# SCH_CANSAT-M2-2026.net
KiCad netlist of a schematic drawn in EasyEDA
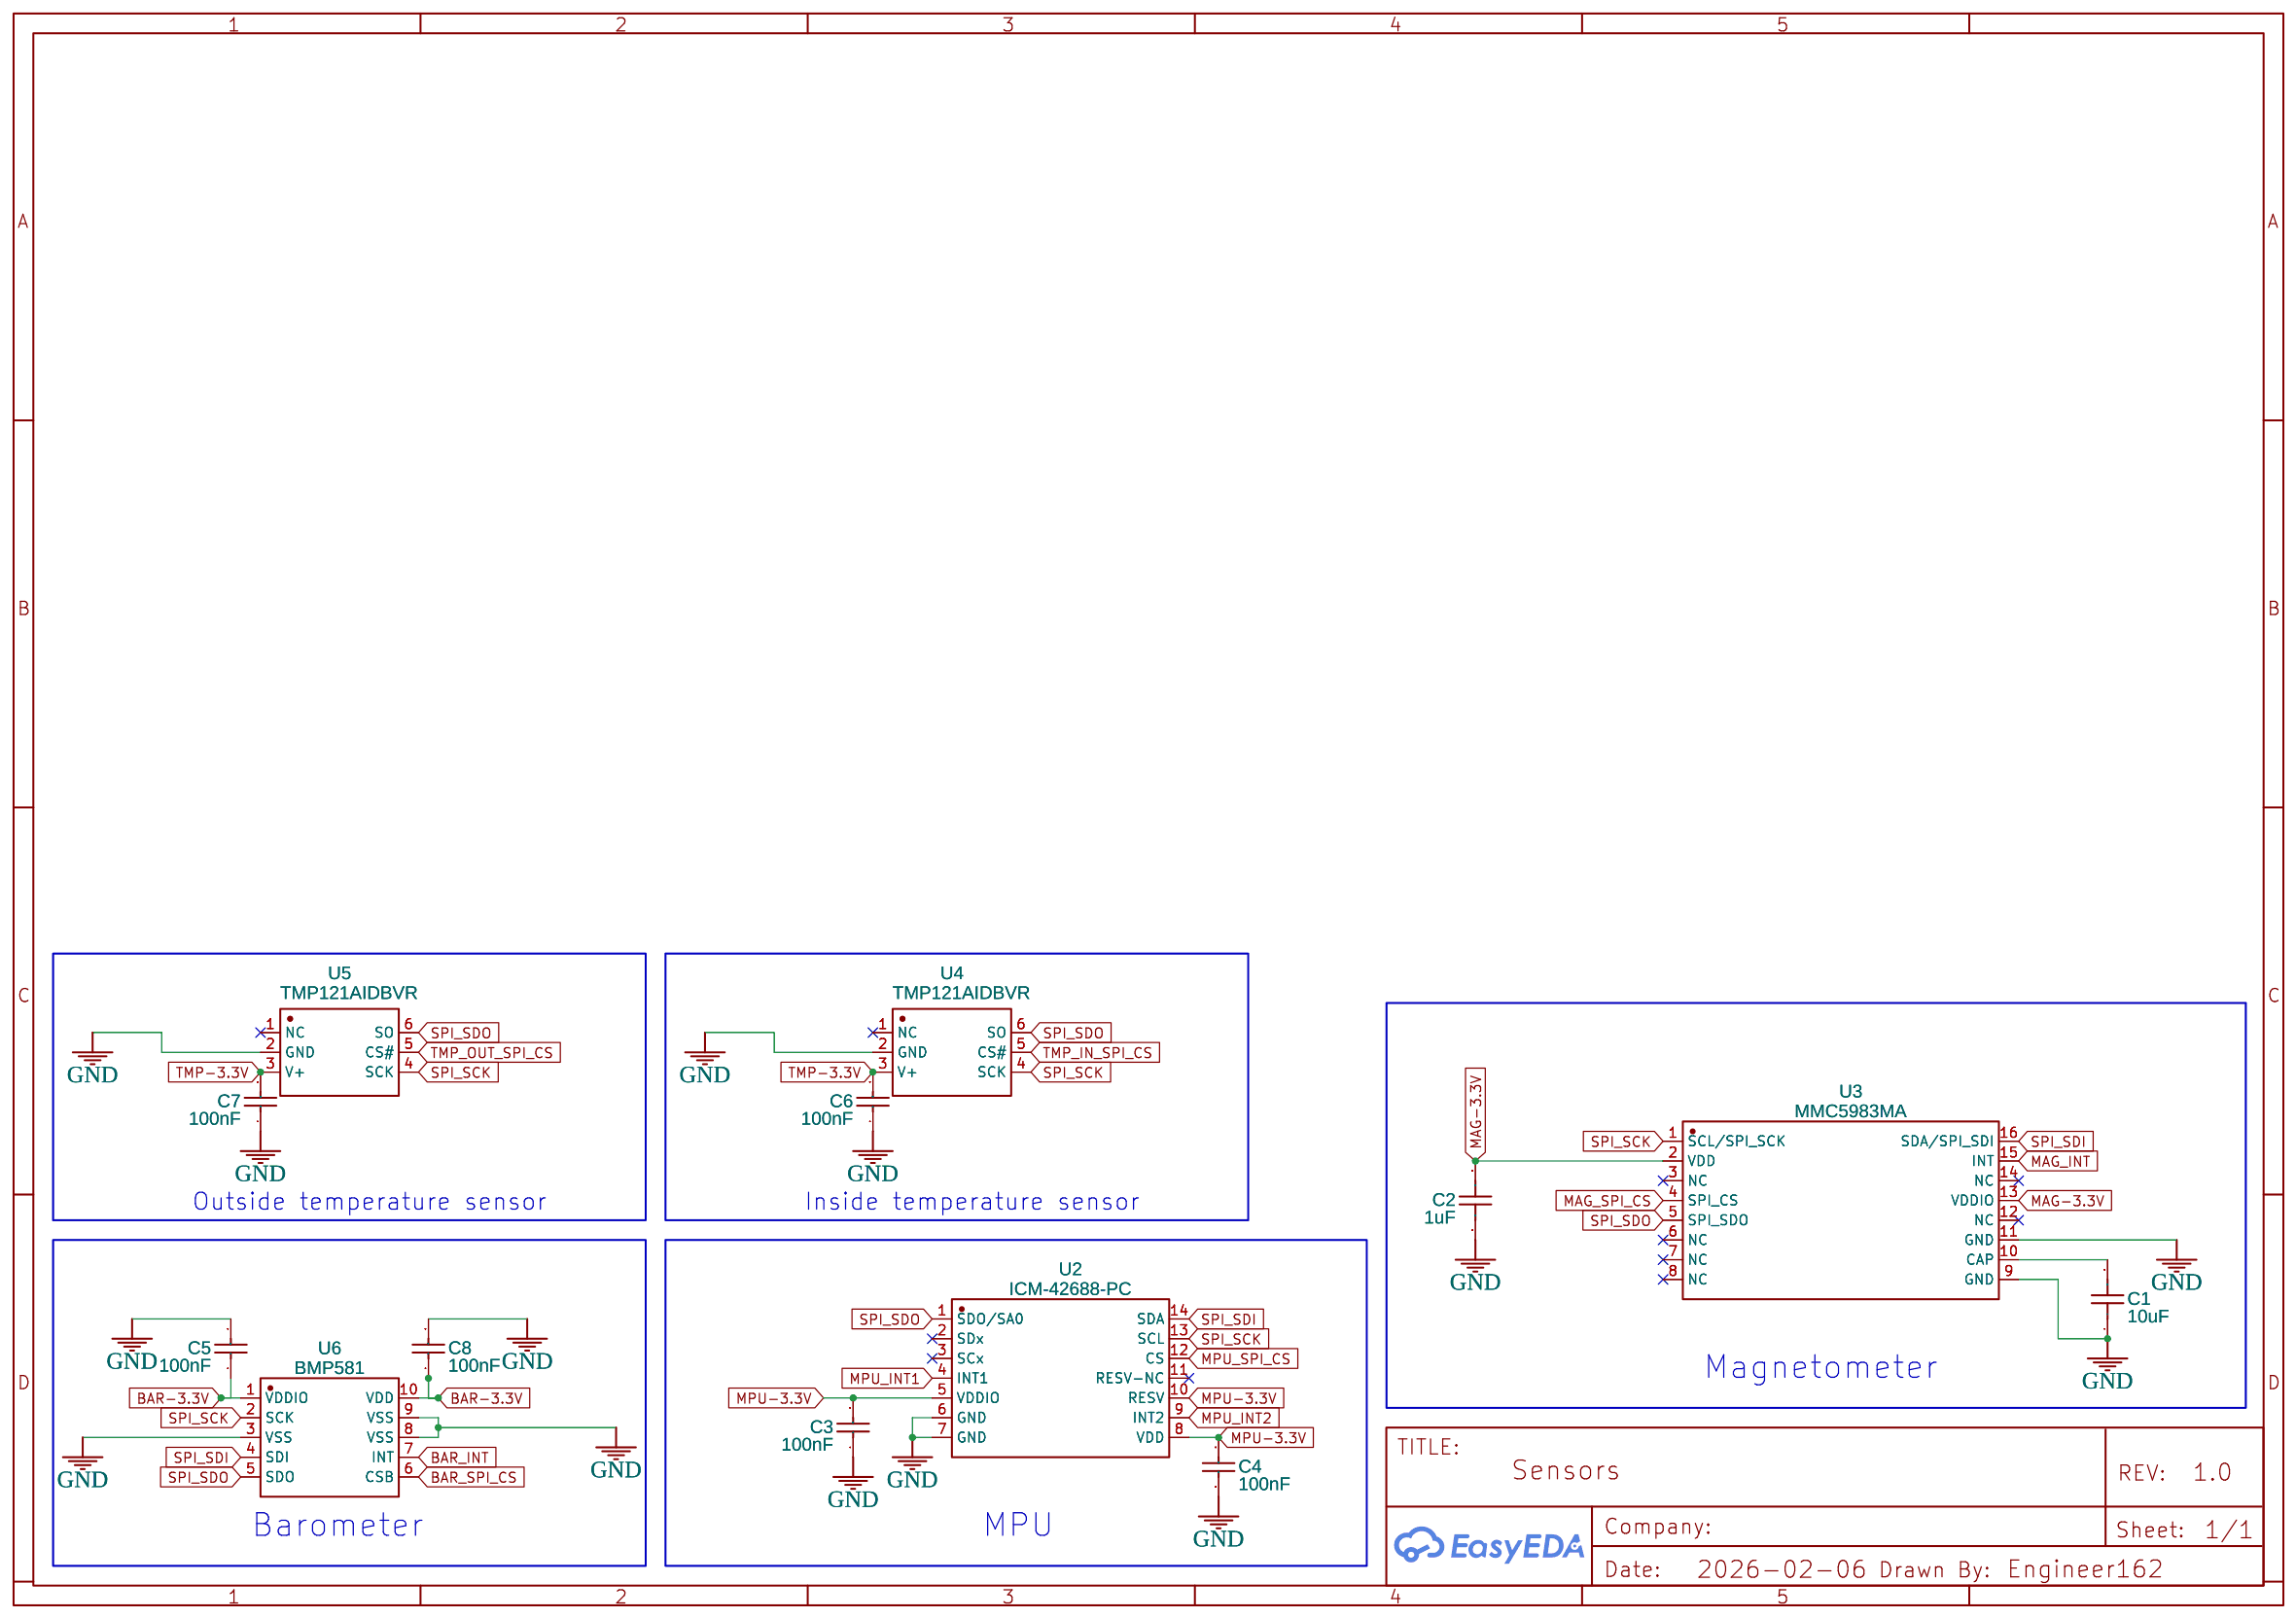
[diagram p0: Sensors]
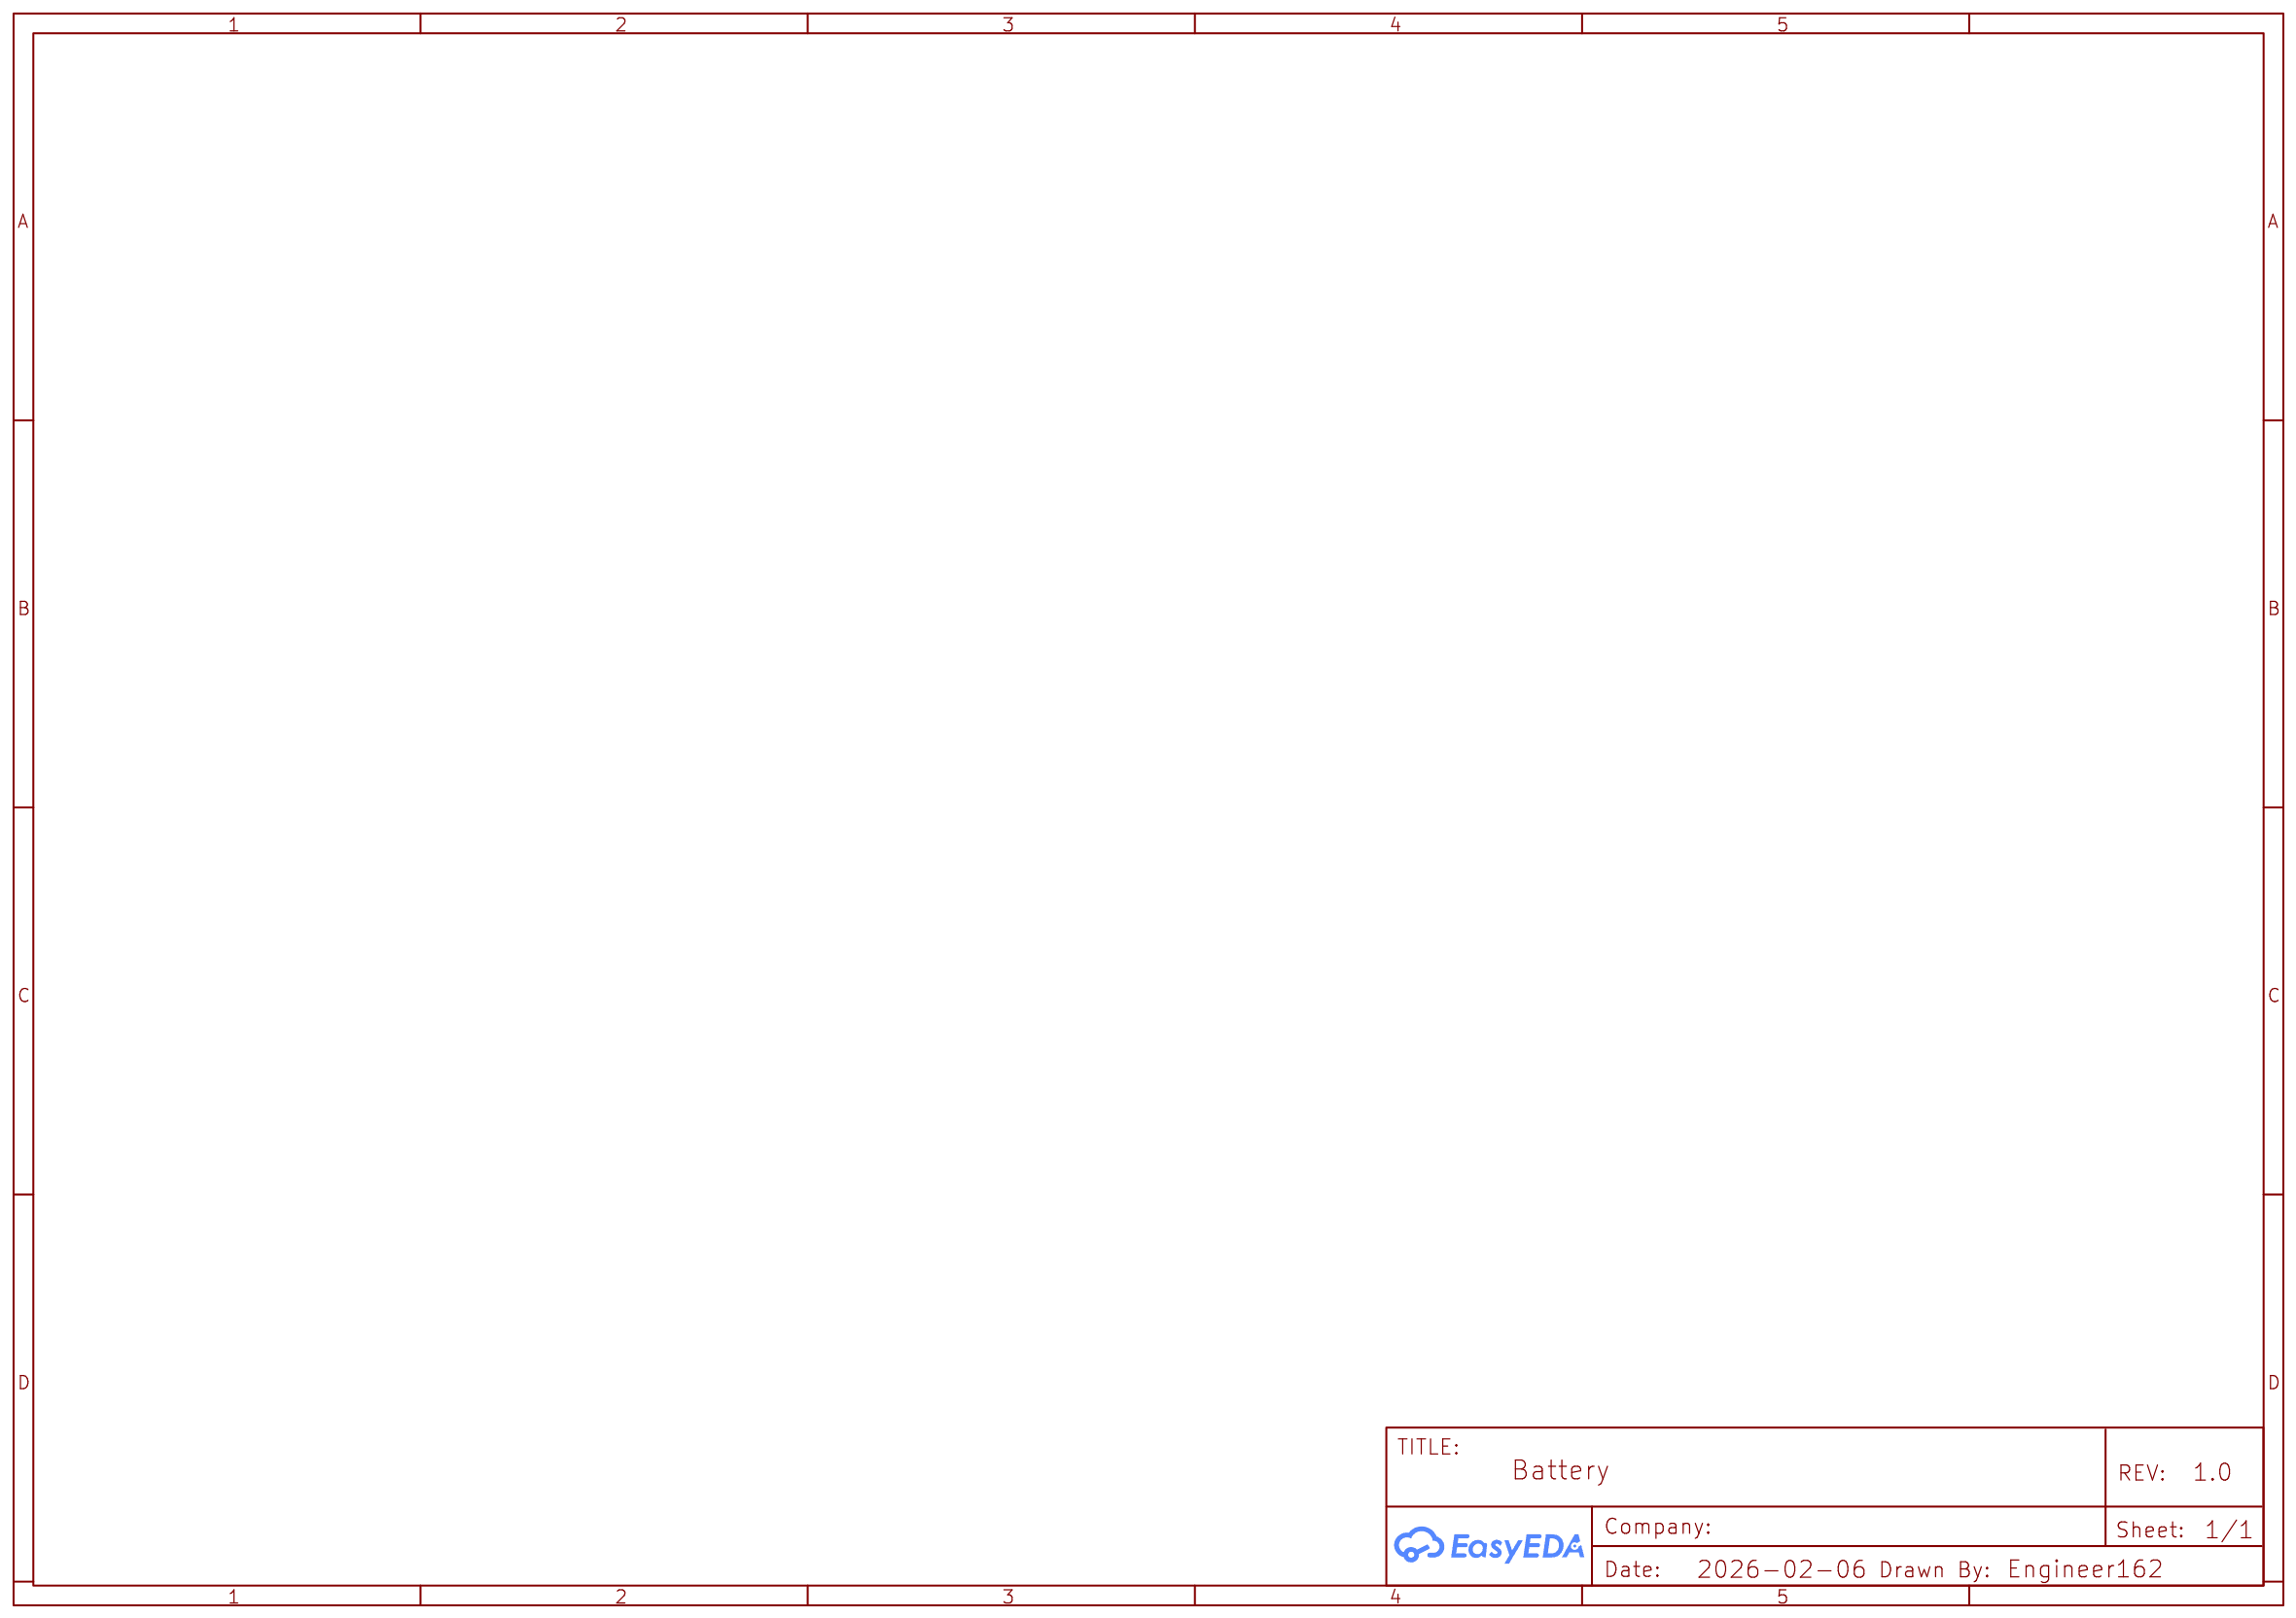
[diagram p1: Battery]
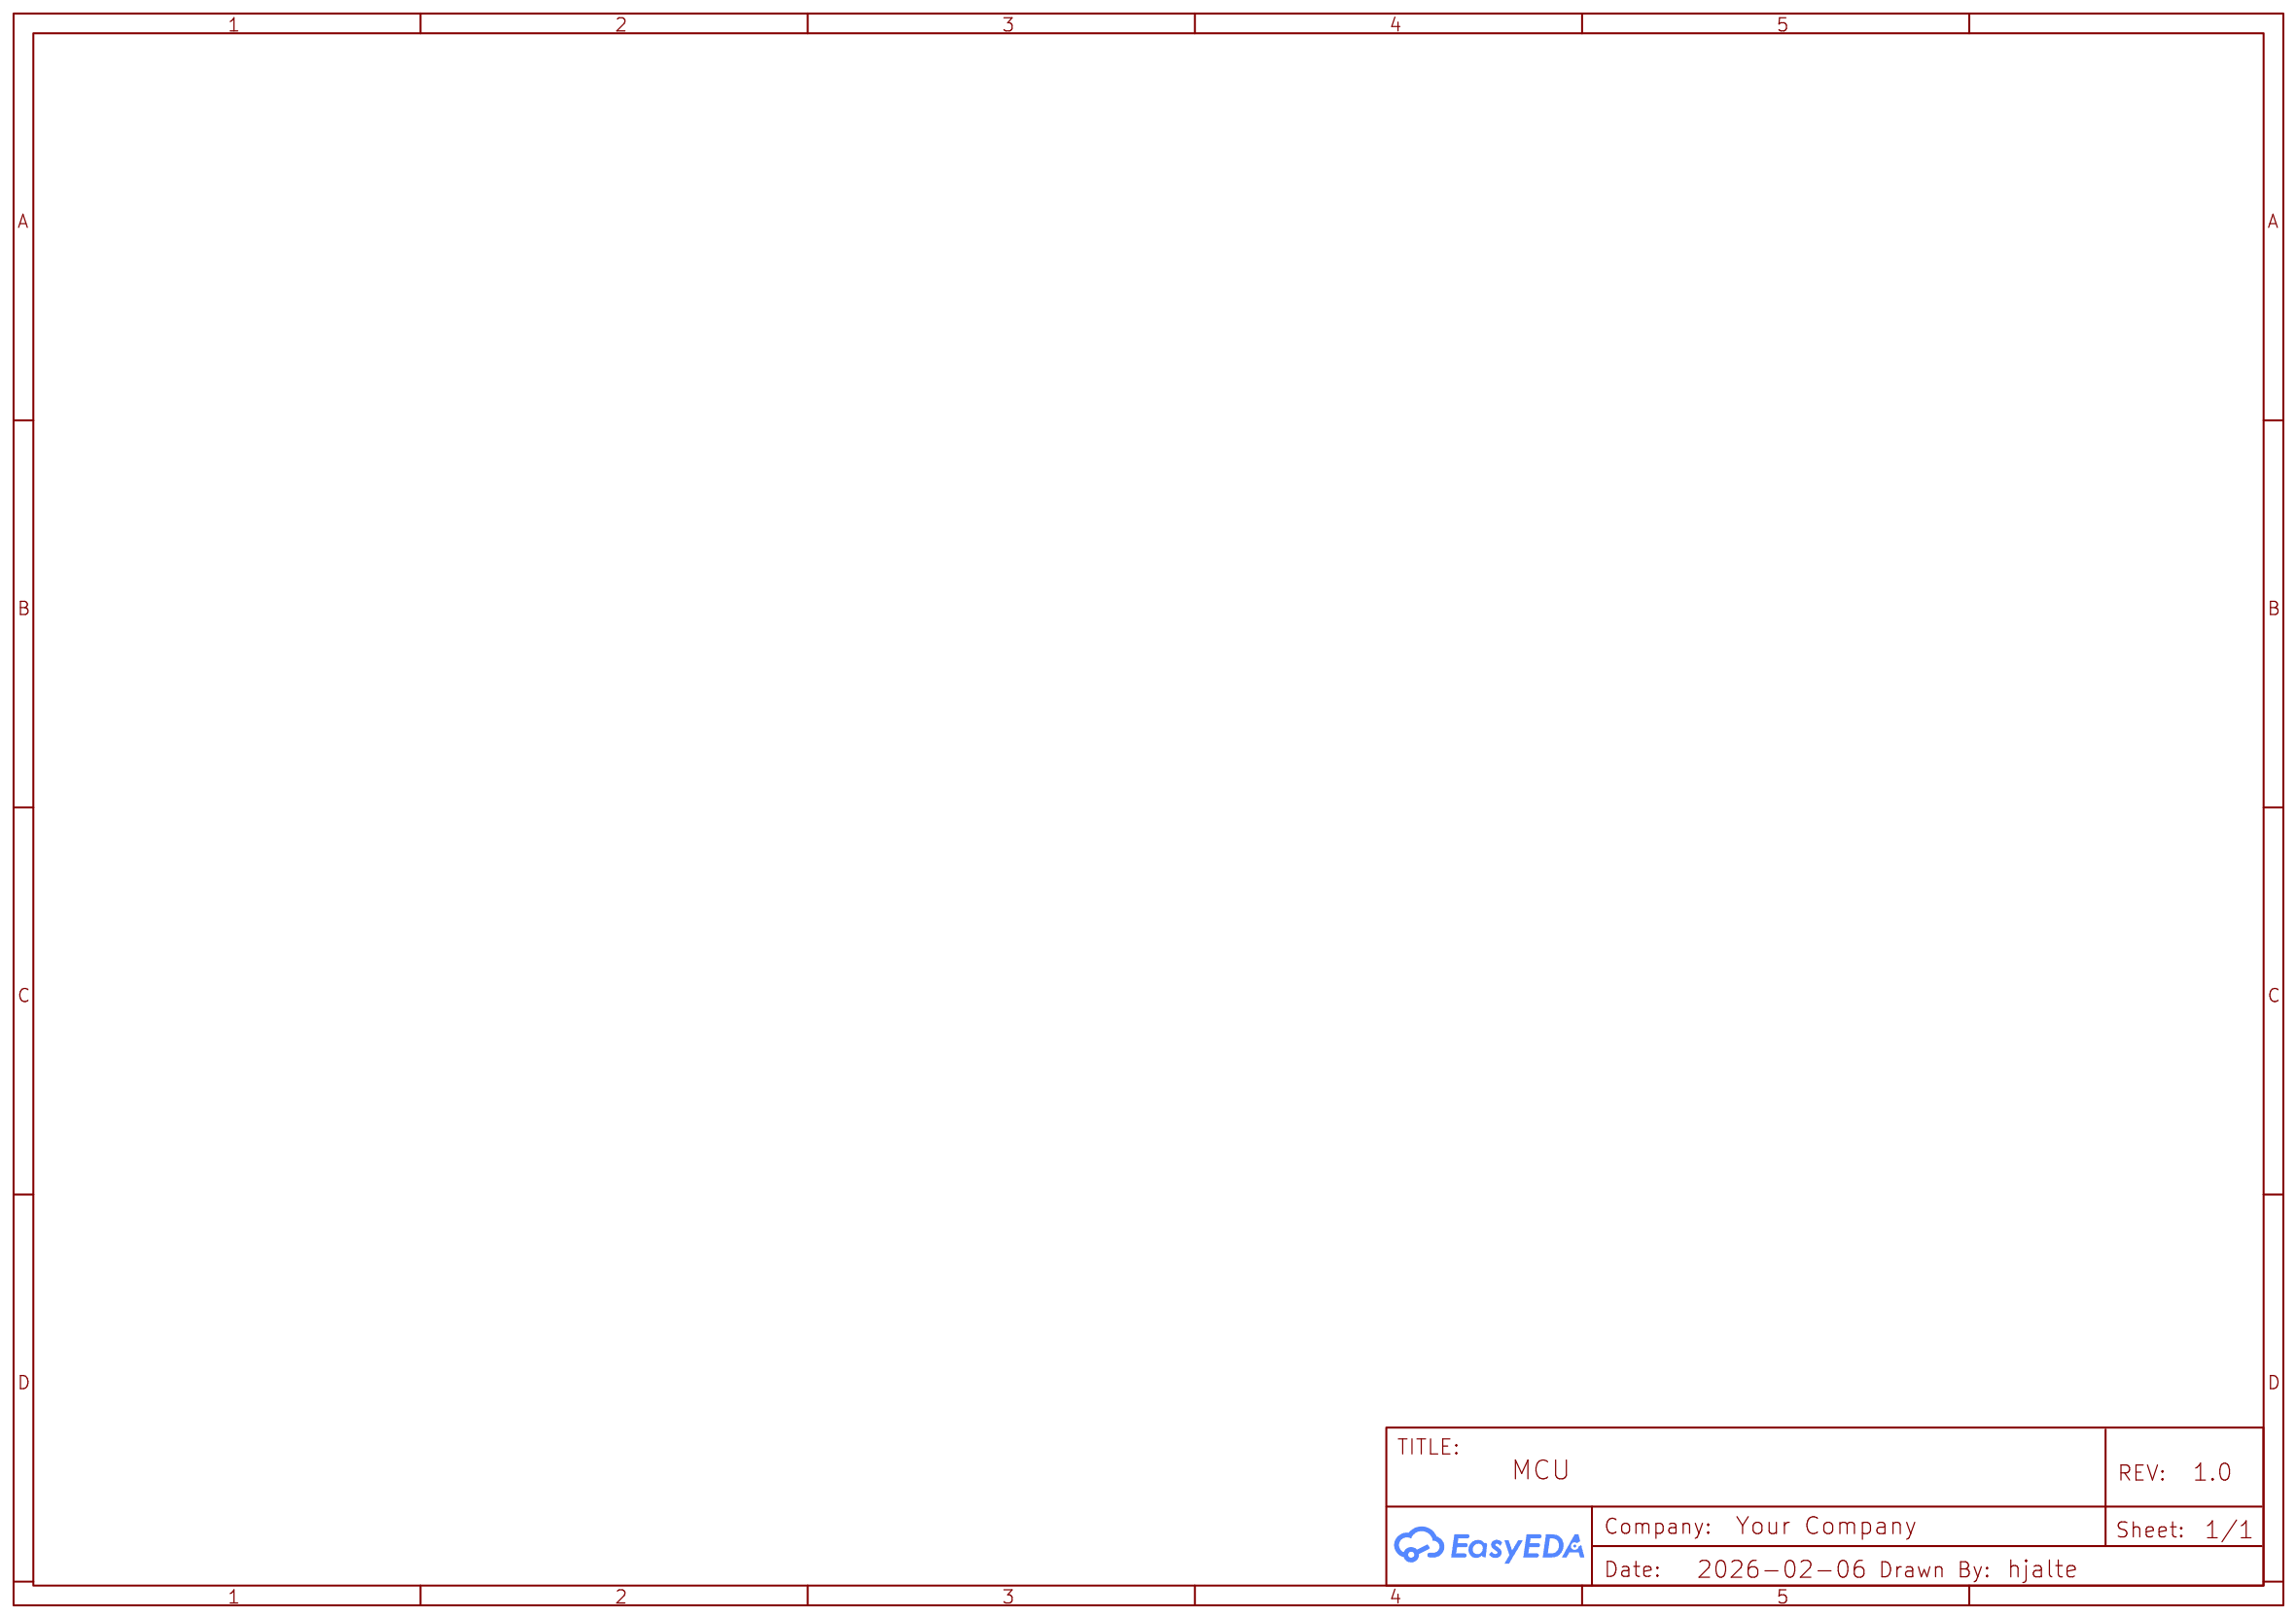
[diagram p2: MCU]

(export (version "E")
  (design (tool "Eeschema 10.0.6"))
  (components
    (comp (ref "C1")
      (value "10uF")
      (fields
        (field (name "Manufacturer Part") "C0805C106J8RACAUTO7210")
        (field (name "Manufacturer") "KEMET(基美)")
      )
      (libsource (lib "") (part "C0805C106J8RACAUTO7210"))
    )
    (comp (ref "C2")
      (value "1uF")
      (fields
        (field (name "Manufacturer Part") "CC0805JKX7R9BB105")
        (field (name "Manufacturer") "YAGEO(国巨)")
      )
      (libsource (lib "") (part "CC0805JKX7R9BB105"))
    )
    (comp (ref "C3")
      (value "100nF")
      (fields
        (field (name "Manufacturer Part") "CL10B104JB8NNNC")
        (field (name "Manufacturer") "SAMSUNG(三星)")
      )
      (libsource (lib "") (part "CL10B104JB8NNNC_1"))
    )
    (comp (ref "C4")
      (value "100nF")
      (fields
        (field (name "Manufacturer Part") "CL10B104JB8NNNC")
        (field (name "Manufacturer") "SAMSUNG(三星)")
      )
      (libsource (lib "") (part "CL10B104JB8NNNC"))
    )
    (comp (ref "C5")
      (value "100nF")
      (fields
        (field (name "Manufacturer Part") "CL10B104JB8NNNC")
        (field (name "Manufacturer") "SAMSUNG(三星)")
      )
      (libsource (lib "") (part "CL10B104JB8NNNC_1"))
    )
    (comp (ref "C6")
      (value "100nF")
      (fields
        (field (name "Manufacturer Part") "CL10B104JB8NNNC")
        (field (name "Manufacturer") "SAMSUNG(三星)")
      )
      (libsource (lib "") (part "CL10B104JB8NNNC_1"))
    )
    (comp (ref "C7")
      (value "100nF")
      (fields
        (field (name "Manufacturer Part") "CL10B104JB8NNNC")
        (field (name "Manufacturer") "SAMSUNG(三星)")
      )
      (libsource (lib "") (part "CL10B104JB8NNNC_1"))
    )
    (comp (ref "C8")
      (value "100nF")
      (fields
        (field (name "Manufacturer Part") "CL10B104JB8NNNC")
        (field (name "Manufacturer") "SAMSUNG(三星)")
      )
      (libsource (lib "") (part "CL10B104JB8NNNC"))
    )
    (comp (ref "U2")
      (value "ICM-42688-PC")
      (fields (field (name "Manufacturer") "Tokmas(托克马斯)"))
      (libsource (lib "") (part "ICM-42688-PC"))
    )
    (comp (ref "U3")
      (value "MMC5983MA")
      (fields (field (name "Manufacturer") "MEMSIC(美新)"))
      (libsource (lib "") (part "MMC5983MA"))
    )
    (comp (ref "U4")
      (value "TMP121AIDBVR")
      (fields (field (name "Manufacturer") "TI(德州仪器)"))
      (libsource (lib "") (part "TMP121AIDBVR"))
    )
    (comp (ref "U5")
      (value "TMP121AIDBVR")
      (fields (field (name "Manufacturer") "TI(德州仪器)"))
      (libsource (lib "") (part "TMP121AIDBVR"))
    )
    (comp (ref "U6")
      (value "BMP581")
      (fields (field (name "Manufacturer") "Bosch(博世)"))
      (libsource (lib "") (part "BMP581"))
    )
  )
  (nets
    (net (code "1") (name "BAR-3.3V") (class "Default")
      (node (ref "C5") (pin "1") (pinfunction "1_1") (pintype "input"))
      (node (ref "C8") (pin "1") (pinfunction "1_1") (pintype "input"))
      (node (ref "U6") (pin "1") (pinfunction "VDDIO_1") (pintype "unspecified"))
      (node (ref "U6") (pin "10") (pinfunction "VDD_10") (pintype "unspecified"))
    )
    (net (code "2") (name "BAR_INT") (class "Default")
      (node (ref "U6") (pin "7") (pinfunction "INT_7") (pintype "unspecified"))
    )
    (net (code "3") (name "BAR_SPI_CS") (class "Default")
      (node (ref "U6") (pin "6") (pinfunction "CSB_6") (pintype "unspecified"))
    )
    (net (code "4") (name "GND") (class "Default")
      (node (ref "C1") (pin "1") (pinfunction "1_1") (pintype "unspecified"))
      (node (ref "C2") (pin "1") (pinfunction "1_1") (pintype "unspecified"))
      (node (ref "C3") (pin "1") (pinfunction "1_1") (pintype "input"))
      (node (ref "C4") (pin "1") (pinfunction "1_1") (pintype "input"))
      (node (ref "C5") (pin "2") (pinfunction "2_2") (pintype "input"))
      (node (ref "C6") (pin "1") (pinfunction "1_1") (pintype "input"))
      (node (ref "C7") (pin "1") (pinfunction "1_1") (pintype "input"))
      (node (ref "C8") (pin "2") (pinfunction "2_2") (pintype "input"))
      (node (ref "U2") (pin "6") (pinfunction "GND_6") (pintype "unspecified"))
      (node (ref "U2") (pin "7") (pinfunction "GND_7") (pintype "unspecified"))
      (node (ref "U3") (pin "11") (pinfunction "GND_11") (pintype "unspecified"))
      (node (ref "U3") (pin "9") (pinfunction "GND_9") (pintype "unspecified"))
      (node (ref "U4") (pin "2") (pinfunction "GND_2") (pintype "unspecified"))
      (node (ref "U5") (pin "2") (pinfunction "GND_2") (pintype "unspecified"))
      (node (ref "U6") (pin "3") (pinfunction "VSS_3") (pintype "unspecified"))
      (node (ref "U6") (pin "8") (pinfunction "VSS_8") (pintype "unspecified"))
      (node (ref "U6") (pin "9") (pinfunction "VSS_9") (pintype "unspecified"))
    )
    (net (code "5") (name "MAG-3.3V") (class "Default")
      (node (ref "C2") (pin "2") (pinfunction "2_2") (pintype "unspecified"))
      (node (ref "U3") (pin "13") (pinfunction "VDDIO_13") (pintype "unspecified"))
      (node (ref "U3") (pin "2") (pinfunction "VDD_2") (pintype "unspecified"))
    )
    (net (code "6") (name "MAG_INT") (class "Default")
      (node (ref "U3") (pin "15") (pinfunction "INT_15") (pintype "unspecified"))
    )
    (net (code "7") (name "MAG_SPI_CS") (class "Default")
      (node (ref "U3") (pin "4") (pinfunction "SPI_CS_4") (pintype "unspecified"))
    )
    (net (code "8") (name "MPU-3.3V") (class "Default")
      (node (ref "C3") (pin "2") (pinfunction "2_2") (pintype "input"))
      (node (ref "C4") (pin "2") (pinfunction "2_2") (pintype "input"))
      (node (ref "U2") (pin "10") (pinfunction "RESV_10") (pintype "unspecified"))
      (node (ref "U2") (pin "5") (pinfunction "VDDIO_5") (pintype "unspecified"))
      (node (ref "U2") (pin "8") (pinfunction "VDD_8") (pintype "unspecified"))
    )
    (net (code "9") (name "MPU_INT1") (class "Default")
      (node (ref "U2") (pin "4") (pinfunction "INT1_4") (pintype "unspecified"))
    )
    (net (code "10") (name "MPU_INT2") (class "Default")
      (node (ref "U2") (pin "9") (pinfunction "INT2_9") (pintype "unspecified"))
    )
    (net (code "11") (name "MPU_SPI_CS") (class "Default")
      (node (ref "U2") (pin "12") (pinfunction "CS_12") (pintype "unspecified"))
    )
    (net (code "12") (name "Net-(U3-CAP)") (class "Default")
      (node (ref "C1") (pin "2") (pinfunction "2_2") (pintype "unspecified"))
      (node (ref "U3") (pin "10") (pinfunction "CAP_10") (pintype "unspecified"))
    )
    (net (code "13") (name "SPI_SCK") (class "Default")
      (node (ref "U2") (pin "13") (pinfunction "SCL_13") (pintype "unspecified"))
      (node (ref "U3") (pin "1") (pinfunction "SCL/SPI_SCK_1") (pintype "unspecified"))
      (node (ref "U4") (pin "4") (pinfunction "SCK_4") (pintype "unspecified"))
      (node (ref "U5") (pin "4") (pinfunction "SCK_4") (pintype "unspecified"))
      (node (ref "U6") (pin "2") (pinfunction "SCK_2") (pintype "unspecified"))
    )
    (net (code "14") (name "SPI_SDI") (class "Default")
      (node (ref "U2") (pin "14") (pinfunction "SDA_14") (pintype "unspecified"))
      (node (ref "U3") (pin "16") (pinfunction "SDA/SPI_SDI_16") (pintype "unspecified"))
      (node (ref "U6") (pin "4") (pinfunction "SDI_4") (pintype "unspecified"))
    )
    (net (code "15") (name "SPI_SDO") (class "Default")
      (node (ref "U2") (pin "1") (pinfunction "SDO/SA0_1") (pintype "unspecified"))
      (node (ref "U3") (pin "5") (pinfunction "SPI_SDO_5") (pintype "unspecified"))
      (node (ref "U4") (pin "6") (pinfunction "SO_6") (pintype "unspecified"))
      (node (ref "U5") (pin "6") (pinfunction "SO_6") (pintype "unspecified"))
      (node (ref "U6") (pin "5") (pinfunction "SDO_5") (pintype "unspecified"))
    )
    (net (code "16") (name "TMP-3.3V") (class "Default")
      (node (ref "C6") (pin "2") (pinfunction "2_2") (pintype "input"))
      (node (ref "C7") (pin "2") (pinfunction "2_2") (pintype "input"))
      (node (ref "U4") (pin "3") (pinfunction "V+_3") (pintype "unspecified"))
      (node (ref "U5") (pin "3") (pinfunction "V+_3") (pintype "unspecified"))
    )
    (net (code "17") (name "TMP_IN_SPI_CS") (class "Default")
      (node (ref "U4") (pin "5") (pinfunction "CS#_5") (pintype "unspecified"))
    )
    (net (code "18") (name "TMP_OUT_SPI_CS") (class "Default")
      (node (ref "U5") (pin "5") (pinfunction "CS#_5") (pintype "unspecified"))
    )
    (net (code "19") (name "unconnected-(U2-RESV-NC-Pad11)") (class "Default")
      (node (ref "U2") (pin "11") (pinfunction "RESV-NC_11") (pintype "unspecified+no_connect"))
    )
    (net (code "20") (name "unconnected-(U2-SCx-Pad3)") (class "Default")
      (node (ref "U2") (pin "3") (pinfunction "SCx_3") (pintype "unspecified+no_connect"))
    )
    (net (code "21") (name "unconnected-(U2-SDx-Pad2)") (class "Default")
      (node (ref "U2") (pin "2") (pinfunction "SDx_2") (pintype "unspecified+no_connect"))
    )
    (net (code "22") (name "unconnected-(U3-NC-Pad3)") (class "Default")
      (node (ref "U3") (pin "3") (pinfunction "NC_3") (pintype "unspecified+no_connect"))
    )
    (net (code "23") (name "unconnected-(U3-NC-Pad6)") (class "Default")
      (node (ref "U3") (pin "6") (pinfunction "NC_6") (pintype "unspecified+no_connect"))
    )
    (net (code "24") (name "unconnected-(U3-NC-Pad7)") (class "Default")
      (node (ref "U3") (pin "7") (pinfunction "NC_7") (pintype "unspecified+no_connect"))
    )
    (net (code "25") (name "unconnected-(U3-NC-Pad8)") (class "Default")
      (node (ref "U3") (pin "8") (pinfunction "NC_8") (pintype "unspecified+no_connect"))
    )
    (net (code "26") (name "unconnected-(U3-NC-Pad12)") (class "Default")
      (node (ref "U3") (pin "12") (pinfunction "NC_12") (pintype "unspecified+no_connect"))
    )
    (net (code "27") (name "unconnected-(U3-NC-Pad14)") (class "Default")
      (node (ref "U3") (pin "14") (pinfunction "NC_14") (pintype "unspecified+no_connect"))
    )
    (net (code "28") (name "unconnected-(U4-NC-Pad1)") (class "Default")
      (node (ref "U4") (pin "1") (pinfunction "NC_1") (pintype "unspecified+no_connect"))
    )
    (net (code "29") (name "unconnected-(U5-NC-Pad1)") (class "Default")
      (node (ref "U5") (pin "1") (pinfunction "NC_1") (pintype "unspecified+no_connect"))
    )
  )
)
